# PSIO_Switchboard_PU-18_v1.net
KiCad netlist of a schematic drawn in EAGLE
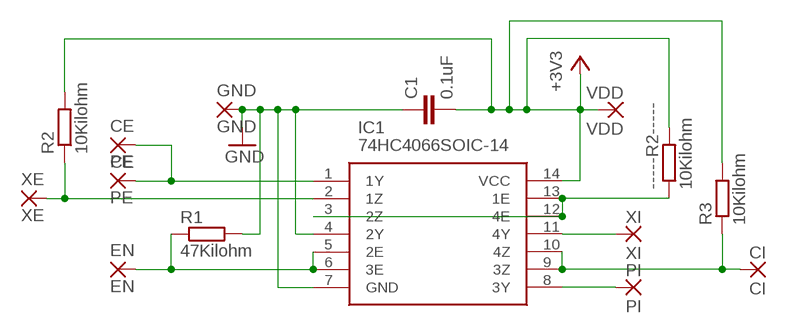
[diagram p0: schematic, sheet 1]

(export (version "E")
  (design (tool "Eeschema 10.0.6"))
  (components
    (comp (ref "-----R2-----")
      (value "10Kilohm")
      (footprint "eagle-import:R0805")
      (libsource (lib "eagle-import") (part "RESISTORSR0805"))
    )
    (comp (ref "C1")
      (value "0.1uF")
      (footprint "eagle-import:C0805")
      (libsource (lib "eagle-import") (part "CAPACITORSC0805"))
    )
    (comp (ref "CE")
      (value "CE")
      (footprint "eagle-import:CIRCLE-2X2")
      (libsource (lib "eagle-import") (part "PADSCIRCLE-2X2"))
    )
    (comp (ref "CI")
      (value "CI")
      (footprint "eagle-import:CIRCLE-2X2")
      (libsource (lib "eagle-import") (part "PADSCIRCLE-2X2"))
    )
    (comp (ref "EN")
      (value "EN")
      (footprint "eagle-import:CIRCLE-2X2")
      (libsource (lib "eagle-import") (part "PADSCIRCLE-2X2"))
    )
    (comp (ref "GND")
      (value "GND")
      (footprint "eagle-import:CIRCLE-2X2")
      (libsource (lib "eagle-import") (part "PADSCIRCLE-2X2"))
    )
    (comp (ref "IC1")
      (value "74HC4066SOIC-14")
      (footprint "eagle-import:SOIC-14")
      (libsource (lib "eagle-import") (part "74HC4066SOIC-14"))
    )
    (comp (ref "PE")
      (value "PE")
      (footprint "eagle-import:CIRCLE-2X2")
      (libsource (lib "eagle-import") (part "PADSCIRCLE-2X2"))
    )
    (comp (ref "PI")
      (value "PI")
      (footprint "eagle-import:CIRCLE-2X2")
      (libsource (lib "eagle-import") (part "PADSCIRCLE-2X2"))
    )
    (comp (ref "R1")
      (value "47Kilohm")
      (footprint "eagle-import:R0805")
      (libsource (lib "eagle-import") (part "RESISTORSR0805"))
    )
    (comp (ref "R2")
      (value "10Kilohm")
      (footprint "eagle-import:R0805")
      (libsource (lib "eagle-import") (part "RESISTORSR0805"))
    )
    (comp (ref "R3")
      (value "10Kilohm")
      (footprint "eagle-import:R0805")
      (libsource (lib "eagle-import") (part "RESISTORSR0805"))
    )
    (comp (ref "VDD")
      (value "VDD")
      (footprint "eagle-import:CIRCLE-2X2")
      (libsource (lib "eagle-import") (part "PADSCIRCLE-2X2"))
    )
    (comp (ref "XE")
      (value "XE")
      (footprint "eagle-import:CIRCLE-2X2")
      (libsource (lib "eagle-import") (part "PADSCIRCLE-2X2"))
    )
    (comp (ref "XI")
      (value "XI")
      (footprint "eagle-import:CIRCLE-2X2")
      (libsource (lib "eagle-import") (part "PADSCIRCLE-2X2"))
    )
  )
  (nets
    (net (code "1") (name "+3V3") (class "Default")
      (node (ref "-----R2-----") (pin "2") (pinfunction "2_2") (pintype "passive"))
      (node (ref "C1") (pin "2") (pinfunction "2_2") (pintype "passive"))
      (node (ref "IC1") (pin "14") (pinfunction "VCC_14") (pintype "bidirectional"))
      (node (ref "R2") (pin "2") (pinfunction "2_2") (pintype "passive"))
      (node (ref "R3") (pin "2") (pinfunction "2_2") (pintype "passive"))
      (node (ref "VDD") (pin "1") (pinfunction "P_1") (pintype "passive"))
    )
    (net (code "2") (name "GND") (class "Default")
      (node (ref "C1") (pin "1") (pinfunction "1_1") (pintype "passive"))
      (node (ref "GND") (pin "1") (pinfunction "P_1") (pintype "passive"))
      (node (ref "IC1") (pin "4") (pinfunction "2Y_4") (pintype "bidirectional"))
      (node (ref "IC1") (pin "7") (pinfunction "GND_7") (pintype "bidirectional"))
      (node (ref "R1") (pin "2") (pinfunction "2_2") (pintype "passive"))
    )
    (net (code "3") (name "Net-(CE-P)") (class "Default")
      (node (ref "CE") (pin "1") (pinfunction "P_1") (pintype "passive"))
      (node (ref "IC1") (pin "1") (pinfunction "1Y_1") (pintype "bidirectional"))
      (node (ref "PE") (pin "1") (pinfunction "P_1") (pintype "passive"))
    )
    (net (code "4") (name "Net-(CI-P)") (class "Default")
      (node (ref "CI") (pin "1") (pinfunction "P_1") (pintype "passive"))
      (node (ref "IC1") (pin "10") (pinfunction "4Z_10") (pintype "bidirectional"))
      (node (ref "IC1") (pin "9") (pinfunction "3Z_9") (pintype "bidirectional"))
      (node (ref "R3") (pin "1") (pinfunction "1_1") (pintype "passive"))
    )
    (net (code "5") (name "Net-(EN-P)") (class "Default")
      (node (ref "EN") (pin "1") (pinfunction "P_1") (pintype "passive"))
      (node (ref "IC1") (pin "5") (pinfunction "2E_5") (pintype "bidirectional"))
      (node (ref "IC1") (pin "6") (pinfunction "3E_6") (pintype "bidirectional"))
      (node (ref "R1") (pin "1") (pinfunction "1_1") (pintype "passive"))
    )
    (net (code "6") (name "Net-(IC1-1E)") (class "Default")
      (node (ref "-----R2-----") (pin "1") (pinfunction "1_1") (pintype "passive"))
      (node (ref "IC1") (pin "12") (pinfunction "4E_12") (pintype "bidirectional"))
      (node (ref "IC1") (pin "13") (pinfunction "1E_13") (pintype "bidirectional"))
      (node (ref "IC1") (pin "3") (pinfunction "2Z_3") (pintype "bidirectional"))
    )
    (net (code "7") (name "Net-(IC1-1Z)") (class "Default")
      (node (ref "IC1") (pin "2") (pinfunction "1Z_2") (pintype "bidirectional"))
      (node (ref "R2") (pin "1") (pinfunction "1_1") (pintype "passive"))
      (node (ref "XE") (pin "1") (pinfunction "P_1") (pintype "passive"))
    )
    (net (code "8") (name "Net-(IC1-3Y)") (class "Default")
      (node (ref "IC1") (pin "8") (pinfunction "3Y_8") (pintype "bidirectional"))
      (node (ref "PI") (pin "1") (pinfunction "P_1") (pintype "passive"))
    )
    (net (code "9") (name "Net-(IC1-4Y)") (class "Default")
      (node (ref "IC1") (pin "11") (pinfunction "4Y_11") (pintype "bidirectional"))
      (node (ref "XI") (pin "1") (pinfunction "P_1") (pintype "passive"))
    )
  )
)
